# saliya.net
KiCad netlist of a schematic drawn in Altium Designer
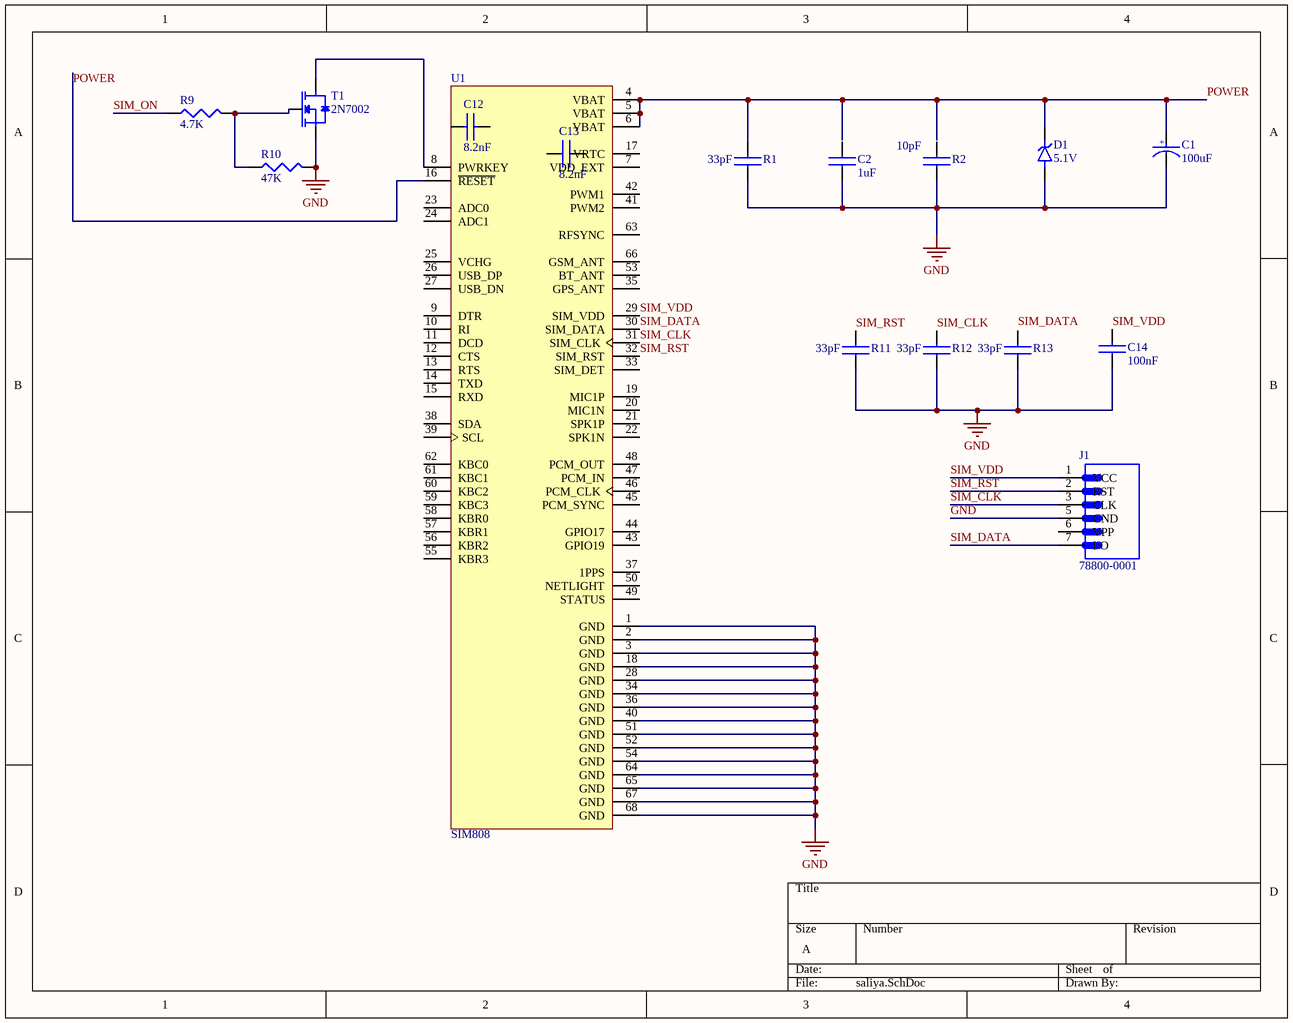
[diagram p0: saliya.SchDoc]

(export (version "E")
  (design (tool "Eeschema 10.0.6"))
  (components
    (comp (ref "C1")
      (value "100uF")
      (footprint "C_ALU_C_SIZE")
      (description "Cap Aluminum 100uF 10V 20% (5 X 5.4mm) SMD 50mA 1000 hr 85°C T/R")
      (fields
        (field (name "MANUFACTURER") "Panasonic")
        (field (name "MANUFACTURER PART NUMBER") "EEE-1AA101WR")
      )
      (libsource (lib "schmaticSMDv1") (part "EEE-1AA101WR"))
    )
    (comp (ref "C2")
      (value "1uF")
      (footprint "C0805")
      (description "0805 1 uF 50 V ±10% Tolerance X7R Multilayer Ceramic Chip Capacitor")
      (fields
        (field (name "MANUFACTURER") "Murata")
        (field (name "MANUFACTURER PART NUMBER") "GRM21BR71H105KA12L")
      )
      (libsource (lib "schmaticSMDv1") (part "GRM21BR71H105KA12L"))
    )
    (comp (ref "C12")
      (value "8.2nF")
      (footprint "C0805")
      (description "CAP CER 0805 8.2NF 16V ULTRA STA")
      (fields
        (field (name "MANUFACTURER") "KEMET")
        (field (name "MANUFACTURER PART NUMBER") "C0805X822F4HAC7800")
      )
      (libsource (lib "schmaticSMDv1") (part "C0805X822F4HAC7800"))
    )
    (comp (ref "C13")
      (value "8.2nF")
      (footprint "C0805")
      (description "CAP CER 0805 8.2NF 16V ULTRA STA")
      (fields
        (field (name "MANUFACTURER") "KEMET")
        (field (name "MANUFACTURER PART NUMBER") "C0805X822F4HAC7800")
      )
      (libsource (lib "schmaticSMDv1") (part "C0805X822F4HAC7800"))
    )
    (comp (ref "C14")
      (value "100nF")
      (footprint "C0805")
      (description "Cap Ceramic 0.1uF 50V X7R 10% Pad SMD 0805 125°C Automotive T/R")
      (fields
        (field (name "MANUFACTURER") "TDK")
        (field (name "MANUFACTURER PART NUMBER") "CGA4J2X7R1H104K125AM")
      )
      (libsource (lib "schmaticSMDv1") (part "CGA4J2X7R1H104K125AM"))
    )
    (comp (ref "D1")
      (value "5.1V")
      (footprint "SOD323")
      (description "Zener Single Diode, 5.1 V, 200 Mw, Sod-323, 6 %, 2, 150 C Rohs Compliant: Yes")
      (fields
        (field (name "MANUFACTURER") "Multicomp")
        (field (name "MANUFACTURER PART NUMBER") "BZT52C5V1S")
      )
      (libsource (lib "schmaticSMDv1") (part "BZT52C5V1S"))
    )
    (comp (ref "J1")
      (value "78800-0001")
      (footprint "SIM")
      (description "Vertical Surface Mount Memory & SIM Card Connector; with SMT Termination")
      (fields (field (name "MANUFACTURER") "Molex"))
      (libsource (lib "schmaticSMDv1") (part "78800-0001"))
    )
    (comp (ref "R1")
      (value "33pF")
      (footprint "C0805")
      (description "0805 33 pF 50 V ±5 % Tolerance NP0 SMT Multilayer Ceramic Capacitor")
      (fields
        (field (name "MANUFACTURER") "Yageo")
        (field (name "MANUFACTURER PART NUMBER") "CC0805JRNPO9BN330")
      )
      (libsource (lib "schmaticSMDv1") (part "CC0805JRNPO9BN330"))
    )
    (comp (ref "R2")
      (value "10pF")
      (footprint "C0805")
      (description "Surface Mount Ceramic Multilayer Capacitor 10pF 5% C0G 50V 0805 Paper T/R")
      (fields
        (field (name "MANUFACTURER") "Yageo")
        (field (name "MANUFACTURER PART NUMBER") "CC0805JRNPO9BN100")
      )
      (libsource (lib "schmaticSMDv1") (part "CC0805JRNPO9BN100"))
    )
    (comp (ref "R9")
      (value "4.7K")
      (footprint "R0805")
      (description "Res Thick Film 0805 4.7K Ohm 5% 0.125W(1/8W) ±100ppm/C Pad SMD T/R")
      (fields
        (field (name "MANUFACTURER") "Yageo")
        (field (name "MANUFACTURER PART NUMBER") "RC0805JR-074K7L")
      )
      (libsource (lib "schmaticSMDv1") (part "RC0805JR-074K7L"))
    )
    (comp (ref "R10")
      (value "47K")
      (footprint "R0805")
      (description "Res Thick Film 0805 47K Ohm 5% 1/8W Ý100ppm/ÝC SMD Paper T/R")
      (fields
        (field (name "MANUFACTURER") "Yageo")
        (field (name "MANUFACTURER PART NUMBER") "RC0805JR-0747KL")
      )
      (libsource (lib "schmaticSMDv1") (part "RC0805JR-0747KL"))
    )
    (comp (ref "R11")
      (value "33pF")
      (footprint "C0805")
      (description "0805 33 pF 50 V ±5 % Tolerance NP0 SMT Multilayer Ceramic Capacitor")
      (fields
        (field (name "MANUFACTURER") "Yageo")
        (field (name "MANUFACTURER PART NUMBER") "CC0805JRNPO9BN330")
      )
      (libsource (lib "schmaticSMDv1") (part "CC0805JRNPO9BN330"))
    )
    (comp (ref "R12")
      (value "33pF")
      (footprint "C0805")
      (description "0805 33 pF 50 V ±5 % Tolerance NP0 SMT Multilayer Ceramic Capacitor")
      (fields
        (field (name "MANUFACTURER") "Yageo")
        (field (name "MANUFACTURER PART NUMBER") "CC0805JRNPO9BN330")
      )
      (libsource (lib "schmaticSMDv1") (part "CC0805JRNPO9BN330"))
    )
    (comp (ref "R13")
      (value "33pF")
      (footprint "C0805")
      (description "0805 33 pF 50 V ±5 % Tolerance NP0 SMT Multilayer Ceramic Capacitor")
      (fields
        (field (name "MANUFACTURER") "Yageo")
        (field (name "MANUFACTURER PART NUMBER") "CC0805JRNPO9BN330")
      )
      (libsource (lib "schmaticSMDv1") (part "CC0805JRNPO9BN330"))
    )
    (comp (ref "T1")
      (value "2N7002")
      (footprint "TRANS_MMBT2907A")
      (description "Transistor Mosfet N-ch 60V 0.3A 3-PIN SOT-23 T/r")
      (libsource (lib "schmaticSMDv1") (part "2N7002"))
    )
    (comp (ref "U1")
      (value "SIM808")
      (footprint "XCVR_SIM808")
      (libsource (lib "schmaticSMDv1") (part "SIM808"))
    )
  )
  (nets
    (net (code "2") (name "/POWER") (class "Default")
      (node (ref "C1") (pin "1") (pinfunction "1_1") (pintype "passive"))
      (node (ref "D1") (pin "C") (pinfunction "K_C") (pintype "passive"))
      (node (ref "R1") (pin "2") (pinfunction "2_2") (pintype "passive"))
      (node (ref "U1") (pin "16") (pinfunction "~{RESET}_16") (pintype "passive"))
      (node (ref "U1") (pin "4") (pinfunction "VBAT_4") (pintype "passive"))
      (node (ref "U1") (pin "5") (pinfunction "VBAT_5") (pintype "passive"))
      (node (ref "U1") (pin "6") (pinfunction "VBAT_6") (pintype "passive"))
    )
    (net (code "3") (name "/SIM_CLK") (class "Default")
      (node (ref "J1") (pin "3") (pinfunction "CLK_3") (pintype "passive"))
      (node (ref "R12") (pin "2") (pinfunction "2_2") (pintype "passive"))
      (node (ref "U1") (pin "31") (pinfunction "SIM_CLK_31") (pintype "passive"))
    )
    (net (code "4") (name "/SIM_DATA") (class "Default")
      (node (ref "J1") (pin "7") (pinfunction "I/O_7") (pintype "passive"))
      (node (ref "U1") (pin "30") (pinfunction "SIM_DATA_30") (pintype "passive"))
    )
    (net (code "5") (name "/SIM_ON") (class "Default")
      (node (ref "R9") (pin "1") (pinfunction "1_1") (pintype "passive"))
    )
    (net (code "6") (name "/SIM_RST") (class "Default")
      (node (ref "J1") (pin "2") (pinfunction "RST_2") (pintype "passive"))
      (node (ref "R11") (pin "2") (pinfunction "2_2") (pintype "passive"))
      (node (ref "U1") (pin "32") (pinfunction "SIM_RST_32") (pintype "passive"))
    )
    (net (code "7") (name "/SIM_VDD") (class "Default")
      (node (ref "C14") (pin "2") (pinfunction "2_2") (pintype "passive"))
      (node (ref "J1") (pin "1") (pinfunction "VCC_1") (pintype "passive"))
      (node (ref "U1") (pin "29") (pinfunction "SIM_VDD_29") (pintype "passive"))
    )
    (net (code "8") (name "GND") (class "Default")
      (node (ref "C1") (pin "2") (pinfunction "2_2") (pintype "passive"))
      (node (ref "C14") (pin "1") (pinfunction "1_1") (pintype "passive"))
      (node (ref "C2") (pin "1") (pinfunction "1_1") (pintype "passive"))
      (node (ref "D1") (pin "A") (pinfunction "A_A") (pintype "passive"))
      (node (ref "J1") (pin "5") (pinfunction "GND_5") (pintype "passive"))
      (node (ref "R1") (pin "1") (pinfunction "1_1") (pintype "passive"))
      (node (ref "R10") (pin "2") (pinfunction "2_2") (pintype "passive"))
      (node (ref "R11") (pin "1") (pinfunction "1_1") (pintype "passive"))
      (node (ref "R12") (pin "1") (pinfunction "1_1") (pintype "passive"))
      (node (ref "R13") (pin "1") (pinfunction "1_1") (pintype "passive"))
      (node (ref "R2") (pin "1") (pinfunction "1_1") (pintype "passive"))
      (node (ref "T1") (pin "1") (pinfunction "1_1") (pintype "passive"))
      (node (ref "U1") (pin "1") (pinfunction "GND_1") (pintype "passive"))
      (node (ref "U1") (pin "18") (pinfunction "GND_18") (pintype "passive"))
      (node (ref "U1") (pin "2") (pinfunction "GND_2") (pintype "passive"))
      (node (ref "U1") (pin "28") (pinfunction "GND_28") (pintype "passive"))
      (node (ref "U1") (pin "3") (pinfunction "GND_3") (pintype "passive"))
      (node (ref "U1") (pin "34") (pinfunction "GND_34") (pintype "passive"))
      (node (ref "U1") (pin "36") (pinfunction "GND_36") (pintype "passive"))
      (node (ref "U1") (pin "40") (pinfunction "GND_40") (pintype "passive"))
      (node (ref "U1") (pin "51") (pinfunction "GND_51") (pintype "passive"))
      (node (ref "U1") (pin "52") (pinfunction "GND_52") (pintype "passive"))
      (node (ref "U1") (pin "54") (pinfunction "GND_54") (pintype "passive"))
      (node (ref "U1") (pin "64") (pinfunction "GND_64") (pintype "passive"))
      (node (ref "U1") (pin "65") (pinfunction "GND_65") (pintype "passive"))
      (node (ref "U1") (pin "67") (pinfunction "GND_67") (pintype "passive"))
      (node (ref "U1") (pin "68") (pinfunction "GND_68") (pintype "passive"))
    )
    (net (code "9") (name "Net-(R10-Pad1)") (class "Default")
      (node (ref "R10") (pin "1") (pinfunction "1_1") (pintype "passive"))
      (node (ref "R9") (pin "2") (pinfunction "2_2") (pintype "passive"))
      (node (ref "T1") (pin "3") (pinfunction "3_3") (pintype "passive"))
    )
    (net (code "10") (name "Net-(U1-PWRKEY)") (class "Default")
      (node (ref "T1") (pin "2") (pinfunction "2_2") (pintype "passive"))
      (node (ref "U1") (pin "8") (pinfunction "PWRKEY_8") (pintype "passive"))
    )
    (net (code "11") (name "unconnected-(C2-Pad2)") (class "Default")
      (node (ref "C2") (pin "2") (pinfunction "2_2") (pintype "passive"))
    )
    (net (code "12") (name "unconnected-(C12-Pad1)") (class "Default")
      (node (ref "C12") (pin "1") (pinfunction "1_1") (pintype "passive"))
    )
    (net (code "13") (name "unconnected-(C12-Pad2)") (class "Default")
      (node (ref "C12") (pin "2") (pinfunction "2_2") (pintype "passive"))
    )
    (net (code "14") (name "unconnected-(C13-Pad1)") (class "Default")
      (node (ref "C13") (pin "1") (pinfunction "1_1") (pintype "passive"))
    )
    (net (code "15") (name "unconnected-(C13-Pad2)") (class "Default")
      (node (ref "C13") (pin "2") (pinfunction "2_2") (pintype "passive"))
    )
    (net (code "16") (name "unconnected-(J1-VPP-Pad6)") (class "Default")
      (node (ref "J1") (pin "6") (pinfunction "VPP_6") (pintype "passive"))
    )
    (net (code "17") (name "unconnected-(R2-Pad2)") (class "Default")
      (node (ref "R2") (pin "2") (pinfunction "2_2") (pintype "passive"))
    )
    (net (code "18") (name "unconnected-(R13-Pad2)") (class "Default")
      (node (ref "R13") (pin "2") (pinfunction "2_2") (pintype "passive"))
    )
    (net (code "19") (name "unconnected-(U1-1PPS-Pad37)") (class "Default")
      (node (ref "U1") (pin "37") (pinfunction "1PPS_37") (pintype "passive"))
    )
    (net (code "20") (name "unconnected-(U1-ADC0-Pad23)") (class "Default")
      (node (ref "U1") (pin "23") (pinfunction "ADC0_23") (pintype "passive"))
    )
    (net (code "21") (name "unconnected-(U1-ADC1-Pad24)") (class "Default")
      (node (ref "U1") (pin "24") (pinfunction "ADC1_24") (pintype "passive"))
    )
    (net (code "22") (name "unconnected-(U1-BT_ANT-Pad53)") (class "Default")
      (node (ref "U1") (pin "53") (pinfunction "BT_ANT_53") (pintype "passive"))
    )
    (net (code "23") (name "unconnected-(U1-CTS-Pad12)") (class "Default")
      (node (ref "U1") (pin "12") (pinfunction "CTS_12") (pintype "passive"))
    )
    (net (code "24") (name "unconnected-(U1-DCD-Pad11)") (class "Default")
      (node (ref "U1") (pin "11") (pinfunction "DCD_11") (pintype "passive"))
    )
    (net (code "25") (name "unconnected-(U1-DTR-Pad9)") (class "Default")
      (node (ref "U1") (pin "9") (pinfunction "DTR_9") (pintype "passive"))
    )
    (net (code "26") (name "unconnected-(U1-GPIO17-Pad44)") (class "Default")
      (node (ref "U1") (pin "44") (pinfunction "GPIO17_44") (pintype "passive"))
    )
    (net (code "27") (name "unconnected-(U1-GPIO19-Pad43)") (class "Default")
      (node (ref "U1") (pin "43") (pinfunction "GPIO19_43") (pintype "passive"))
    )
    (net (code "28") (name "unconnected-(U1-GPS_ANT-Pad35)") (class "Default")
      (node (ref "U1") (pin "35") (pinfunction "GPS_ANT_35") (pintype "passive"))
    )
    (net (code "29") (name "unconnected-(U1-GSM_ANT-Pad66)") (class "Default")
      (node (ref "U1") (pin "66") (pinfunction "GSM_ANT_66") (pintype "passive"))
    )
    (net (code "30") (name "unconnected-(U1-KBC0-Pad62)") (class "Default")
      (node (ref "U1") (pin "62") (pinfunction "KBC0_62") (pintype "passive"))
    )
    (net (code "31") (name "unconnected-(U1-KBC1-Pad61)") (class "Default")
      (node (ref "U1") (pin "61") (pinfunction "KBC1_61") (pintype "passive"))
    )
    (net (code "32") (name "unconnected-(U1-KBC2-Pad60)") (class "Default")
      (node (ref "U1") (pin "60") (pinfunction "KBC2_60") (pintype "passive"))
    )
    (net (code "33") (name "unconnected-(U1-KBC3-Pad59)") (class "Default")
      (node (ref "U1") (pin "59") (pinfunction "KBC3_59") (pintype "passive"))
    )
    (net (code "34") (name "unconnected-(U1-KBR0-Pad58)") (class "Default")
      (node (ref "U1") (pin "58") (pinfunction "KBR0_58") (pintype "passive"))
    )
    (net (code "35") (name "unconnected-(U1-KBR1-Pad57)") (class "Default")
      (node (ref "U1") (pin "57") (pinfunction "KBR1_57") (pintype "passive"))
    )
    (net (code "36") (name "unconnected-(U1-KBR2-Pad56)") (class "Default")
      (node (ref "U1") (pin "56") (pinfunction "KBR2_56") (pintype "passive"))
    )
    (net (code "37") (name "unconnected-(U1-KBR3-Pad55)") (class "Default")
      (node (ref "U1") (pin "55") (pinfunction "KBR3_55") (pintype "passive"))
    )
    (net (code "38") (name "unconnected-(U1-MIC1N-Pad20)") (class "Default")
      (node (ref "U1") (pin "20") (pinfunction "MIC1N_20") (pintype "passive"))
    )
    (net (code "39") (name "unconnected-(U1-MIC1P-Pad19)") (class "Default")
      (node (ref "U1") (pin "19") (pinfunction "MIC1P_19") (pintype "passive"))
    )
    (net (code "40") (name "unconnected-(U1-NETLIGHT-Pad50)") (class "Default")
      (node (ref "U1") (pin "50") (pinfunction "NETLIGHT_50") (pintype "passive"))
    )
    (net (code "41") (name "unconnected-(U1-PCM_CLK-Pad46)") (class "Default")
      (node (ref "U1") (pin "46") (pinfunction "PCM_CLK_46") (pintype "passive"))
    )
    (net (code "42") (name "unconnected-(U1-PCM_IN-Pad47)") (class "Default")
      (node (ref "U1") (pin "47") (pinfunction "PCM_IN_47") (pintype "passive"))
    )
    (net (code "43") (name "unconnected-(U1-PCM_OUT-Pad48)") (class "Default")
      (node (ref "U1") (pin "48") (pinfunction "PCM_OUT_48") (pintype "passive"))
    )
    (net (code "44") (name "unconnected-(U1-PCM_SYNC-Pad45)") (class "Default")
      (node (ref "U1") (pin "45") (pinfunction "PCM_SYNC_45") (pintype "passive"))
    )
    (net (code "45") (name "unconnected-(U1-PWM1-Pad42)") (class "Default")
      (node (ref "U1") (pin "42") (pinfunction "PWM1_42") (pintype "passive"))
    )
    (net (code "46") (name "unconnected-(U1-PWM2-Pad41)") (class "Default")
      (node (ref "U1") (pin "41") (pinfunction "PWM2_41") (pintype "passive"))
    )
    (net (code "47") (name "unconnected-(U1-RFSYNC-Pad63)") (class "Default")
      (node (ref "U1") (pin "63") (pinfunction "RFSYNC_63") (pintype "passive"))
    )
    (net (code "48") (name "unconnected-(U1-RI-Pad10)") (class "Default")
      (node (ref "U1") (pin "10") (pinfunction "RI_10") (pintype "passive"))
    )
    (net (code "49") (name "unconnected-(U1-RTS-Pad13)") (class "Default")
      (node (ref "U1") (pin "13") (pinfunction "RTS_13") (pintype "passive"))
    )
    (net (code "50") (name "unconnected-(U1-RXD-Pad15)") (class "Default")
      (node (ref "U1") (pin "15") (pinfunction "RXD_15") (pintype "passive"))
    )
    (net (code "51") (name "unconnected-(U1-SCL-Pad39)") (class "Default")
      (node (ref "U1") (pin "39") (pinfunction "SCL_39") (pintype "passive"))
    )
    (net (code "52") (name "unconnected-(U1-SDA-Pad38)") (class "Default")
      (node (ref "U1") (pin "38") (pinfunction "SDA_38") (pintype "passive"))
    )
    (net (code "53") (name "unconnected-(U1-SIM_DET-Pad33)") (class "Default")
      (node (ref "U1") (pin "33") (pinfunction "SIM_DET_33") (pintype "passive"))
    )
    (net (code "54") (name "unconnected-(U1-SPK1N-Pad22)") (class "Default")
      (node (ref "U1") (pin "22") (pinfunction "SPK1N_22") (pintype "passive"))
    )
    (net (code "55") (name "unconnected-(U1-SPK1P-Pad21)") (class "Default")
      (node (ref "U1") (pin "21") (pinfunction "SPK1P_21") (pintype "passive"))
    )
    (net (code "56") (name "unconnected-(U1-STATUS-Pad49)") (class "Default")
      (node (ref "U1") (pin "49") (pinfunction "STATUS_49") (pintype "passive"))
    )
    (net (code "57") (name "unconnected-(U1-TXD-Pad14)") (class "Default")
      (node (ref "U1") (pin "14") (pinfunction "TXD_14") (pintype "passive"))
    )
    (net (code "58") (name "unconnected-(U1-USB_DN-Pad27)") (class "Default")
      (node (ref "U1") (pin "27") (pinfunction "USB_DN_27") (pintype "passive"))
    )
    (net (code "59") (name "unconnected-(U1-USB_DP-Pad26)") (class "Default")
      (node (ref "U1") (pin "26") (pinfunction "USB_DP_26") (pintype "passive"))
    )
    (net (code "60") (name "unconnected-(U1-VCHG-Pad25)") (class "Default")
      (node (ref "U1") (pin "25") (pinfunction "VCHG_25") (pintype "passive"))
    )
    (net (code "61") (name "unconnected-(U1-VDD_EXT-Pad7)") (class "Default")
      (node (ref "U1") (pin "7") (pinfunction "VDD_EXT_7") (pintype "passive"))
    )
    (net (code "62") (name "unconnected-(U1-VRTC-Pad17)") (class "Default")
      (node (ref "U1") (pin "17") (pinfunction "VRTC_17") (pintype "passive"))
    )
  )
)
